# Spaceship_Controller.net
KiCad netlist of a schematic drawn in EAGLE
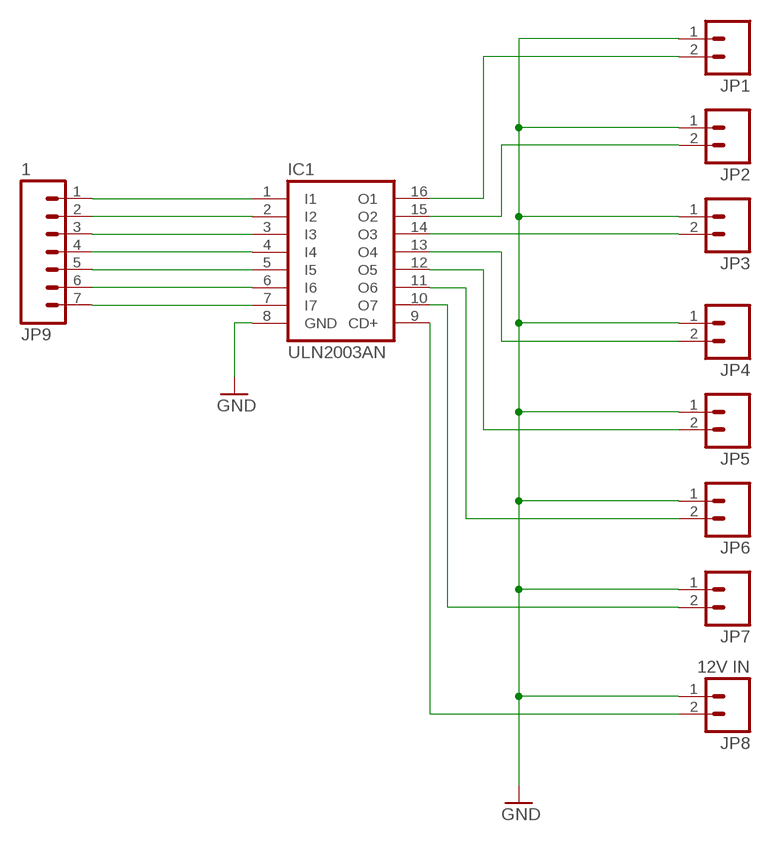
[diagram p0: schematic, sheet 1]

(export (version "E")
  (design (tool "Eeschema 10.0.6"))
  (components
    (comp (ref "IC1")
      (value "ULN2003AN")
      (footprint "eagle-import:DIL16")
      (libsource (lib "eagle-import") (part "ULN2003AN"))
    )
    (comp (ref "JP1")
      (value "M023.5MM_LOCK")
      (footprint "eagle-import:SCREWTERMINAL-3.5MM-2_LOCK")
      (libsource (lib "eagle-import") (part "M023.5MM_LOCK"))
    )
    (comp (ref "JP2")
      (value "M023.5MM_LOCK")
      (footprint "eagle-import:SCREWTERMINAL-3.5MM-2_LOCK")
      (libsource (lib "eagle-import") (part "M023.5MM_LOCK"))
    )
    (comp (ref "JP3")
      (value "M023.5MM_LOCK")
      (footprint "eagle-import:SCREWTERMINAL-3.5MM-2_LOCK")
      (libsource (lib "eagle-import") (part "M023.5MM_LOCK"))
    )
    (comp (ref "JP4")
      (value "M023.5MM_LOCK")
      (footprint "eagle-import:SCREWTERMINAL-3.5MM-2_LOCK")
      (libsource (lib "eagle-import") (part "M023.5MM_LOCK"))
    )
    (comp (ref "JP5")
      (value "M023.5MM_LOCK")
      (footprint "eagle-import:SCREWTERMINAL-3.5MM-2_LOCK")
      (libsource (lib "eagle-import") (part "M023.5MM_LOCK"))
    )
    (comp (ref "JP6")
      (value "M023.5MM_LOCK")
      (footprint "eagle-import:SCREWTERMINAL-3.5MM-2_LOCK")
      (libsource (lib "eagle-import") (part "M023.5MM_LOCK"))
    )
    (comp (ref "JP7")
      (value "M023.5MM_LOCK")
      (footprint "eagle-import:SCREWTERMINAL-3.5MM-2_LOCK")
      (libsource (lib "eagle-import") (part "M023.5MM_LOCK"))
    )
    (comp (ref "JP8")
      (value "12V IN")
      (footprint "eagle-import:SCREWTERMINAL-3.5MM-2_LOCK")
      (libsource (lib "eagle-import") (part "M023.5MM_LOCK"))
    )
    (comp (ref "JP9")
      (value "1")
      (footprint "eagle-import:1X07_LONGPADS")
      (libsource (lib "eagle-import") (part "M07LONGPADS"))
    )
  )
  (nets
    (net (code "1") (name "GND") (class "Default")
      (node (ref "IC1") (pin "8") (pinfunction "GND_8") (pintype "power_in"))
      (node (ref "JP1") (pin "1") (pinfunction "1_1") (pintype "passive"))
      (node (ref "JP2") (pin "1") (pinfunction "1_1") (pintype "passive"))
      (node (ref "JP3") (pin "1") (pinfunction "1_1") (pintype "passive"))
      (node (ref "JP4") (pin "1") (pinfunction "1_1") (pintype "passive"))
      (node (ref "JP5") (pin "1") (pinfunction "1_1") (pintype "passive"))
      (node (ref "JP6") (pin "1") (pinfunction "1_1") (pintype "passive"))
      (node (ref "JP7") (pin "1") (pinfunction "1_1") (pintype "passive"))
      (node (ref "JP8") (pin "1") (pinfunction "1_1") (pintype "passive"))
    )
    (net (code "2") (name "Net-(IC1-CD+)") (class "Default")
      (node (ref "IC1") (pin "9") (pinfunction "CD+_9") (pintype "passive"))
      (node (ref "JP8") (pin "2") (pinfunction "2_2") (pintype "passive"))
    )
    (net (code "3") (name "Net-(IC1-I1)") (class "Default")
      (node (ref "IC1") (pin "1") (pinfunction "I1_1") (pintype "input"))
      (node (ref "JP9") (pin "1") (pinfunction "1_1") (pintype "passive"))
    )
    (net (code "4") (name "Net-(IC1-I2)") (class "Default")
      (node (ref "IC1") (pin "2") (pinfunction "I2_2") (pintype "input"))
      (node (ref "JP9") (pin "2") (pinfunction "2_2") (pintype "passive"))
    )
    (net (code "5") (name "Net-(IC1-I3)") (class "Default")
      (node (ref "IC1") (pin "3") (pinfunction "I3_3") (pintype "input"))
      (node (ref "JP9") (pin "3") (pinfunction "3_3") (pintype "passive"))
    )
    (net (code "6") (name "Net-(IC1-I4)") (class "Default")
      (node (ref "IC1") (pin "4") (pinfunction "I4_4") (pintype "input"))
      (node (ref "JP9") (pin "4") (pinfunction "4_4") (pintype "passive"))
    )
    (net (code "7") (name "Net-(IC1-I5)") (class "Default")
      (node (ref "IC1") (pin "5") (pinfunction "I5_5") (pintype "input"))
      (node (ref "JP9") (pin "5") (pinfunction "5_5") (pintype "passive"))
    )
    (net (code "8") (name "Net-(IC1-I6)") (class "Default")
      (node (ref "IC1") (pin "6") (pinfunction "I6_6") (pintype "input"))
      (node (ref "JP9") (pin "6") (pinfunction "6_6") (pintype "passive"))
    )
    (net (code "9") (name "Net-(IC1-I7)") (class "Default")
      (node (ref "IC1") (pin "7") (pinfunction "I7_7") (pintype "input"))
      (node (ref "JP9") (pin "7") (pinfunction "7_7") (pintype "passive"))
    )
    (net (code "10") (name "Net-(IC1-O1)") (class "Default")
      (node (ref "IC1") (pin "16") (pinfunction "O1_16") (pintype "open_collector"))
      (node (ref "JP1") (pin "2") (pinfunction "2_2") (pintype "passive"))
    )
    (net (code "11") (name "Net-(IC1-O2)") (class "Default")
      (node (ref "IC1") (pin "15") (pinfunction "O2_15") (pintype "open_collector"))
      (node (ref "JP2") (pin "2") (pinfunction "2_2") (pintype "passive"))
    )
    (net (code "12") (name "Net-(IC1-O3)") (class "Default")
      (node (ref "IC1") (pin "14") (pinfunction "O3_14") (pintype "open_collector"))
      (node (ref "JP3") (pin "2") (pinfunction "2_2") (pintype "passive"))
    )
    (net (code "13") (name "Net-(IC1-O4)") (class "Default")
      (node (ref "IC1") (pin "13") (pinfunction "O4_13") (pintype "open_collector"))
      (node (ref "JP4") (pin "2") (pinfunction "2_2") (pintype "passive"))
    )
    (net (code "14") (name "Net-(IC1-O5)") (class "Default")
      (node (ref "IC1") (pin "12") (pinfunction "O5_12") (pintype "open_collector"))
      (node (ref "JP5") (pin "2") (pinfunction "2_2") (pintype "passive"))
    )
    (net (code "15") (name "Net-(IC1-O6)") (class "Default")
      (node (ref "IC1") (pin "11") (pinfunction "O6_11") (pintype "open_collector"))
      (node (ref "JP6") (pin "2") (pinfunction "2_2") (pintype "passive"))
    )
    (net (code "16") (name "Net-(IC1-O7)") (class "Default")
      (node (ref "IC1") (pin "10") (pinfunction "O7_10") (pintype "open_collector"))
      (node (ref "JP7") (pin "2") (pinfunction "2_2") (pintype "passive"))
    )
  )
)
